# SG1000_-_SMS_PP.net
KiCad netlist of a schematic drawn in EAGLE
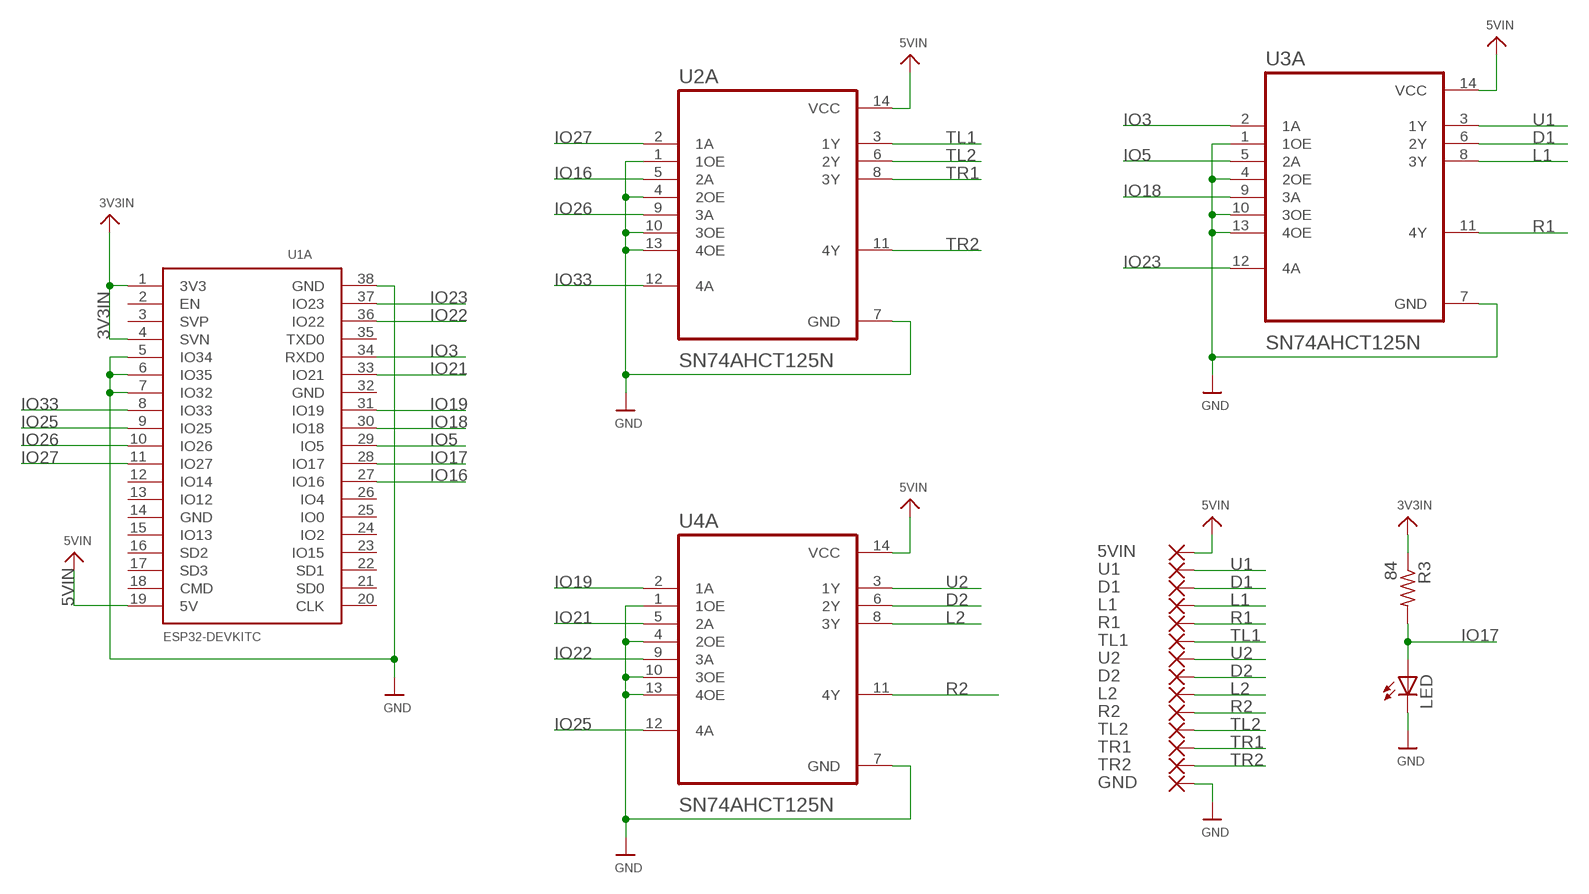
[diagram p0: schematic, sheet 1]

(export (version "E")
  (design (tool "Eeschema 10.0.6"))
  (components
    (comp (ref "5VIN")
      (value "SMD5")
      (footprint "eagle-import:SMD2,54-5,08")
      (libsource (lib "eagle-import") (part "SMD5"))
    )
    (comp (ref "D1")
      (value "SMD5")
      (footprint "eagle-import:SMD2,54-5,08")
      (libsource (lib "eagle-import") (part "SMD5"))
    )
    (comp (ref "D2")
      (value "SMD5")
      (footprint "eagle-import:SMD2,54-5,08")
      (libsource (lib "eagle-import") (part "SMD5"))
    )
    (comp (ref "GND")
      (value "SMD5")
      (footprint "eagle-import:SMD2,54-5,08")
      (libsource (lib "eagle-import") (part "SMD5"))
    )
    (comp (ref "L1")
      (value "SMD5")
      (footprint "eagle-import:SMD2,54-5,08")
      (libsource (lib "eagle-import") (part "SMD5"))
    )
    (comp (ref "L2")
      (value "SMD5")
      (footprint "eagle-import:SMD2,54-5,08")
      (libsource (lib "eagle-import") (part "SMD5"))
    )
    (comp (ref "LED")
      (value "LEDCHIPLED_1206")
      (footprint "eagle-import:CHIPLED_1206")
      (libsource (lib "eagle-import") (part "LEDCHIPLED_1206"))
    )
    (comp (ref "R1")
      (value "SMD5")
      (footprint "eagle-import:SMD2,54-5,08")
      (libsource (lib "eagle-import") (part "SMD5"))
    )
    (comp (ref "R2")
      (value "SMD5")
      (footprint "eagle-import:SMD2,54-5,08")
      (libsource (lib "eagle-import") (part "SMD5"))
    )
    (comp (ref "R3")
      (value "84")
      (footprint "eagle-import:R1206")
      (libsource (lib "eagle-import") (part "R-US_R1206"))
    )
    (comp (ref "TL1")
      (value "SMD5")
      (footprint "eagle-import:SMD2,54-5,08")
      (libsource (lib "eagle-import") (part "SMD5"))
    )
    (comp (ref "TL2")
      (value "SMD5")
      (footprint "eagle-import:SMD2,54-5,08")
      (libsource (lib "eagle-import") (part "SMD5"))
    )
    (comp (ref "TR1")
      (value "SMD5")
      (footprint "eagle-import:SMD2,54-5,08")
      (libsource (lib "eagle-import") (part "SMD5"))
    )
    (comp (ref "TR2")
      (value "SMD5")
      (footprint "eagle-import:SMD2,54-5,08")
      (libsource (lib "eagle-import") (part "SMD5"))
    )
    (comp (ref "U1")
      (value "SMD5")
      (footprint "eagle-import:SMD2,54-5,08")
      (libsource (lib "eagle-import") (part "SMD5"))
    )
    (comp (ref "U1A")
      (value "ESP32DEVKITC")
      (footprint "eagle-import:ESP32-DEVKITC")
      (libsource (lib "eagle-import") (part "ESP32DEVKITC"))
    )
    (comp (ref "U2")
      (value "SMD5")
      (footprint "eagle-import:SMD2,54-5,08")
      (libsource (lib "eagle-import") (part "SMD5"))
    )
    (comp (ref "U2A")
      (value "SN74AHCT125N")
      (footprint "eagle-import:DIP794W45P254L1969H508Q14")
      (fields (field (name "MF") "Texas Instruments"))
      (libsource (lib "eagle-import") (part "SN74AHCT125N"))
    )
    (comp (ref "U3A")
      (value "SN74AHCT125N")
      (footprint "eagle-import:DIP794W45P254L1969H508Q14")
      (fields (field (name "MF") "Texas Instruments"))
      (libsource (lib "eagle-import") (part "SN74AHCT125N"))
    )
    (comp (ref "U4A")
      (value "SN74AHCT125N")
      (footprint "eagle-import:DIP794W45P254L1969H508Q14")
      (fields (field (name "MF") "Texas Instruments"))
      (libsource (lib "eagle-import") (part "SN74AHCT125N"))
    )
  )
  (nets
    (net (code "1") (name "/D1") (class "Default")
      (node (ref "D1") (pin "1") (pinfunction "P_1") (pintype "passive"))
      (node (ref "U3A") (pin "6") (pinfunction "2Y_6") (pintype "output"))
    )
    (net (code "2") (name "/D2") (class "Default")
      (node (ref "D2") (pin "1") (pinfunction "P_1") (pintype "passive"))
      (node (ref "U4A") (pin "6") (pinfunction "2Y_6") (pintype "output"))
    )
    (net (code "3") (name "/IO3") (class "Default")
      (node (ref "U1A") (pin "34") (pinfunction "RXD0_34") (pintype "bidirectional"))
      (node (ref "U3A") (pin "2") (pinfunction "1A_2") (pintype "input"))
    )
    (net (code "4") (name "/IO5") (class "Default")
      (node (ref "U1A") (pin "29") (pinfunction "IO5_29") (pintype "bidirectional"))
      (node (ref "U3A") (pin "5") (pinfunction "2A_5") (pintype "input"))
    )
    (net (code "5") (name "/IO16") (class "Default")
      (node (ref "U1A") (pin "27") (pinfunction "IO16_27") (pintype "bidirectional"))
      (node (ref "U2A") (pin "5") (pinfunction "2A_5") (pintype "input"))
    )
    (net (code "6") (name "/IO17") (class "Default")
      (node (ref "LED") (pin "A") (pinfunction "A_A") (pintype "passive"))
      (node (ref "R3") (pin "2") (pinfunction "2_2") (pintype "passive"))
      (node (ref "U1A") (pin "28") (pinfunction "IO17_28") (pintype "bidirectional"))
    )
    (net (code "7") (name "/IO18") (class "Default")
      (node (ref "U1A") (pin "30") (pinfunction "IO18_30") (pintype "bidirectional"))
      (node (ref "U3A") (pin "9") (pinfunction "3A_9") (pintype "input"))
    )
    (net (code "8") (name "/IO19") (class "Default")
      (node (ref "U1A") (pin "31") (pinfunction "IO19_31") (pintype "bidirectional"))
      (node (ref "U4A") (pin "2") (pinfunction "1A_2") (pintype "input"))
    )
    (net (code "9") (name "/IO21") (class "Default")
      (node (ref "U1A") (pin "33") (pinfunction "IO21_33") (pintype "bidirectional"))
      (node (ref "U4A") (pin "5") (pinfunction "2A_5") (pintype "input"))
    )
    (net (code "10") (name "/IO22") (class "Default")
      (node (ref "U1A") (pin "36") (pinfunction "IO22_36") (pintype "bidirectional"))
      (node (ref "U4A") (pin "9") (pinfunction "3A_9") (pintype "input"))
    )
    (net (code "11") (name "/IO23") (class "Default")
      (node (ref "U1A") (pin "37") (pinfunction "IO23_37") (pintype "bidirectional"))
      (node (ref "U3A") (pin "12") (pinfunction "4A_12") (pintype "bidirectional"))
    )
    (net (code "12") (name "/IO25") (class "Default")
      (node (ref "U1A") (pin "9") (pinfunction "IO25_9") (pintype "bidirectional"))
      (node (ref "U4A") (pin "12") (pinfunction "4A_12") (pintype "bidirectional"))
    )
    (net (code "13") (name "/IO26") (class "Default")
      (node (ref "U1A") (pin "10") (pinfunction "IO26_10") (pintype "bidirectional"))
      (node (ref "U2A") (pin "9") (pinfunction "3A_9") (pintype "input"))
    )
    (net (code "14") (name "/IO27") (class "Default")
      (node (ref "U1A") (pin "11") (pinfunction "IO27_11") (pintype "bidirectional"))
      (node (ref "U2A") (pin "2") (pinfunction "1A_2") (pintype "input"))
    )
    (net (code "15") (name "/IO33") (class "Default")
      (node (ref "U1A") (pin "8") (pinfunction "IO33_8") (pintype "bidirectional"))
      (node (ref "U2A") (pin "12") (pinfunction "4A_12") (pintype "bidirectional"))
    )
    (net (code "16") (name "/L1") (class "Default")
      (node (ref "L1") (pin "1") (pinfunction "P_1") (pintype "passive"))
      (node (ref "U3A") (pin "8") (pinfunction "3Y_8") (pintype "output"))
    )
    (net (code "17") (name "/L2") (class "Default")
      (node (ref "L2") (pin "1") (pinfunction "P_1") (pintype "passive"))
      (node (ref "U4A") (pin "8") (pinfunction "3Y_8") (pintype "output"))
    )
    (net (code "18") (name "/R1") (class "Default")
      (node (ref "R1") (pin "1") (pinfunction "P_1") (pintype "passive"))
      (node (ref "U3A") (pin "11") (pinfunction "4Y_11") (pintype "output"))
    )
    (net (code "19") (name "/R2") (class "Default")
      (node (ref "R2") (pin "1") (pinfunction "P_1") (pintype "passive"))
      (node (ref "U4A") (pin "11") (pinfunction "4Y_11") (pintype "output"))
    )
    (net (code "20") (name "/TL1") (class "Default")
      (node (ref "TL1") (pin "1") (pinfunction "P_1") (pintype "passive"))
      (node (ref "U2A") (pin "3") (pinfunction "1Y_3") (pintype "output"))
    )
    (net (code "21") (name "/TL2") (class "Default")
      (node (ref "TL2") (pin "1") (pinfunction "P_1") (pintype "passive"))
      (node (ref "U2A") (pin "6") (pinfunction "2Y_6") (pintype "output"))
    )
    (net (code "22") (name "/TR1") (class "Default")
      (node (ref "TR1") (pin "1") (pinfunction "P_1") (pintype "passive"))
      (node (ref "U2A") (pin "8") (pinfunction "3Y_8") (pintype "output"))
    )
    (net (code "23") (name "/TR2") (class "Default")
      (node (ref "TR2") (pin "1") (pinfunction "P_1") (pintype "passive"))
      (node (ref "U2A") (pin "11") (pinfunction "4Y_11") (pintype "output"))
    )
    (net (code "24") (name "/U1") (class "Default")
      (node (ref "U1") (pin "1") (pinfunction "P_1") (pintype "passive"))
      (node (ref "U3A") (pin "3") (pinfunction "1Y_3") (pintype "output"))
    )
    (net (code "25") (name "/U2") (class "Default")
      (node (ref "U2") (pin "1") (pinfunction "P_1") (pintype "passive"))
      (node (ref "U4A") (pin "3") (pinfunction "1Y_3") (pintype "output"))
    )
    (net (code "26") (name "3V3IN") (class "Default")
      (node (ref "R3") (pin "1") (pinfunction "1_1") (pintype "passive"))
      (node (ref "U1A") (pin "1") (pinfunction "3V3_1") (pintype "bidirectional"))
      (node (ref "U1A") (pin "4") (pinfunction "SVN_4") (pintype "bidirectional"))
    )
    (net (code "27") (name "5VIN") (class "Default")
      (node (ref "5VIN") (pin "1") (pinfunction "P_1") (pintype "passive"))
      (node (ref "U1A") (pin "19") (pinfunction "5V_19") (pintype "bidirectional"))
      (node (ref "U2A") (pin "14") (pinfunction "VCC_14") (pintype "power_in"))
      (node (ref "U3A") (pin "14") (pinfunction "VCC_14") (pintype "power_in"))
      (node (ref "U4A") (pin "14") (pinfunction "VCC_14") (pintype "power_in"))
    )
    (net (code "28") (name "GND") (class "Default")
      (node (ref "GND") (pin "1") (pinfunction "P_1") (pintype "passive"))
      (node (ref "LED") (pin "C") (pinfunction "C_C") (pintype "passive"))
      (node (ref "U1A") (pin "38") (pinfunction "GND_38") (pintype "bidirectional"))
      (node (ref "U1A") (pin "5") (pinfunction "IO34_5") (pintype "bidirectional"))
      (node (ref "U1A") (pin "6") (pinfunction "IO35_6") (pintype "bidirectional"))
      (node (ref "U1A") (pin "7") (pinfunction "IO32_7") (pintype "bidirectional"))
      (node (ref "U2A") (pin "1") (pinfunction "1OE_1") (pintype "input"))
      (node (ref "U2A") (pin "10") (pinfunction "3OE_10") (pintype "input"))
      (node (ref "U2A") (pin "13") (pinfunction "4OE_13") (pintype "input"))
      (node (ref "U2A") (pin "4") (pinfunction "2OE_4") (pintype "input"))
      (node (ref "U2A") (pin "7") (pinfunction "GND_7") (pintype "power_in"))
      (node (ref "U3A") (pin "1") (pinfunction "1OE_1") (pintype "input"))
      (node (ref "U3A") (pin "10") (pinfunction "3OE_10") (pintype "input"))
      (node (ref "U3A") (pin "13") (pinfunction "4OE_13") (pintype "input"))
      (node (ref "U3A") (pin "4") (pinfunction "2OE_4") (pintype "input"))
      (node (ref "U3A") (pin "7") (pinfunction "GND_7") (pintype "power_in"))
      (node (ref "U4A") (pin "1") (pinfunction "1OE_1") (pintype "input"))
      (node (ref "U4A") (pin "10") (pinfunction "3OE_10") (pintype "input"))
      (node (ref "U4A") (pin "13") (pinfunction "4OE_13") (pintype "input"))
      (node (ref "U4A") (pin "4") (pinfunction "2OE_4") (pintype "input"))
      (node (ref "U4A") (pin "7") (pinfunction "GND_7") (pintype "power_in"))
    )
    (net (code "29") (name "unconnected-(U1A-CLK-Pad20)") (class "Default")
      (node (ref "U1A") (pin "20") (pinfunction "CLK_20") (pintype "bidirectional"))
    )
    (net (code "30") (name "unconnected-(U1A-CMD-Pad18)") (class "Default")
      (node (ref "U1A") (pin "18") (pinfunction "CMD_18") (pintype "bidirectional"))
    )
    (net (code "31") (name "unconnected-(U1A-EN-Pad2)") (class "Default")
      (node (ref "U1A") (pin "2") (pinfunction "EN_2") (pintype "bidirectional"))
    )
    (net (code "32") (name "unconnected-(U1A-GND-Pad14)") (class "Default")
      (node (ref "U1A") (pin "14") (pinfunction "GND_14") (pintype "bidirectional"))
    )
    (net (code "33") (name "unconnected-(U1A-GND-Pad32)") (class "Default")
      (node (ref "U1A") (pin "32") (pinfunction "GND_32") (pintype "bidirectional"))
    )
    (net (code "34") (name "unconnected-(U1A-IO0-Pad25)") (class "Default")
      (node (ref "U1A") (pin "25") (pinfunction "IO0_25") (pintype "bidirectional"))
    )
    (net (code "35") (name "unconnected-(U1A-IO2-Pad24)") (class "Default")
      (node (ref "U1A") (pin "24") (pinfunction "IO2_24") (pintype "bidirectional"))
    )
    (net (code "36") (name "unconnected-(U1A-IO4-Pad26)") (class "Default")
      (node (ref "U1A") (pin "26") (pinfunction "IO4_26") (pintype "bidirectional"))
    )
    (net (code "37") (name "unconnected-(U1A-IO12-Pad13)") (class "Default")
      (node (ref "U1A") (pin "13") (pinfunction "IO12_13") (pintype "bidirectional"))
    )
    (net (code "38") (name "unconnected-(U1A-IO13-Pad15)") (class "Default")
      (node (ref "U1A") (pin "15") (pinfunction "IO13_15") (pintype "bidirectional"))
    )
    (net (code "39") (name "unconnected-(U1A-IO14-Pad12)") (class "Default")
      (node (ref "U1A") (pin "12") (pinfunction "IO14_12") (pintype "bidirectional"))
    )
    (net (code "40") (name "unconnected-(U1A-IO15-Pad23)") (class "Default")
      (node (ref "U1A") (pin "23") (pinfunction "IO15_23") (pintype "bidirectional"))
    )
    (net (code "41") (name "unconnected-(U1A-SD0-Pad21)") (class "Default")
      (node (ref "U1A") (pin "21") (pinfunction "SD0_21") (pintype "bidirectional"))
    )
    (net (code "42") (name "unconnected-(U1A-SD1-Pad22)") (class "Default")
      (node (ref "U1A") (pin "22") (pinfunction "SD1_22") (pintype "bidirectional"))
    )
    (net (code "43") (name "unconnected-(U1A-SD2-Pad16)") (class "Default")
      (node (ref "U1A") (pin "16") (pinfunction "SD2_16") (pintype "bidirectional"))
    )
    (net (code "44") (name "unconnected-(U1A-SD3-Pad17)") (class "Default")
      (node (ref "U1A") (pin "17") (pinfunction "SD3_17") (pintype "bidirectional"))
    )
    (net (code "45") (name "unconnected-(U1A-SVP-Pad3)") (class "Default")
      (node (ref "U1A") (pin "3") (pinfunction "SVP_3") (pintype "bidirectional"))
    )
    (net (code "46") (name "unconnected-(U1A-TXD0-Pad35)") (class "Default")
      (node (ref "U1A") (pin "35") (pinfunction "TXD0_35") (pintype "bidirectional"))
    )
  )
)
